# riffle-CT-beta-0_1_0.net
KiCad netlist of a schematic drawn in EAGLE
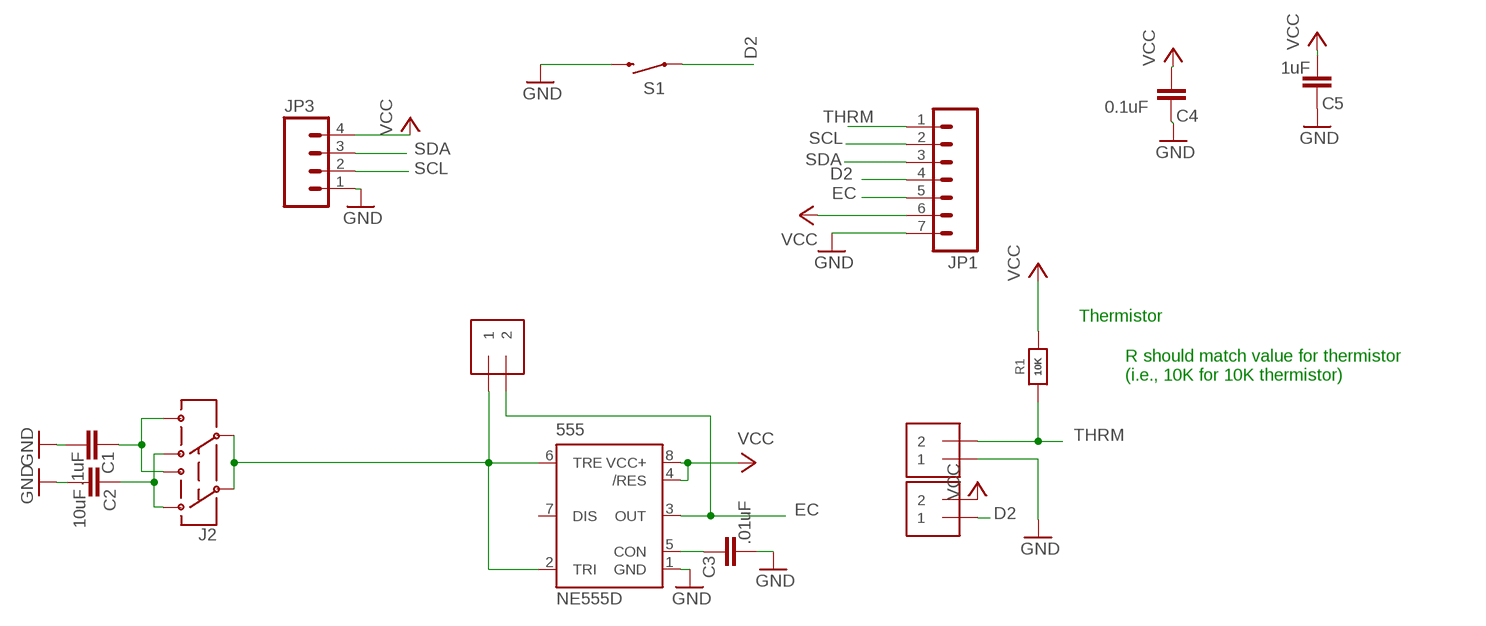
[diagram p0: schematic, sheet 1]

(export (version "E")
  (design (tool "Eeschema 10.0.6"))
  (components
    (comp (ref "1W")
      (value "1X2-3.5MM")
      (footprint "eagle-import:1X2-3.5MM")
      (libsource (lib "eagle-import") (part "1X2-3.5MM"))
    )
    (comp (ref "555")
      (value "NE555D")
      (footprint "eagle-import:SO08@1")
      (libsource (lib "eagle-import") (part "NE555D"))
    )
    (comp (ref "C1")
      (value ".1uF")
      (footprint "eagle-import:0603-CAP")
      (libsource (lib "eagle-import") (part "CAP0603-CAP"))
    )
    (comp (ref "C2")
      (value "10uF")
      (footprint "eagle-import:0603-CAP")
      (libsource (lib "eagle-import") (part "CAP0603-CAP"))
    )
    (comp (ref "C3")
      (value ".01uF")
      (footprint "eagle-import:0603-CAP")
      (libsource (lib "eagle-import") (part "CAP0603-CAP"))
    )
    (comp (ref "C4")
      (value "0.1uF")
      (footprint "eagle-import:0603-CAP")
      (libsource (lib "eagle-import") (part "CAP0603-CAP"))
    )
    (comp (ref "C5")
      (value "1uF")
      (footprint "eagle-import:0603-CAP")
      (libsource (lib "eagle-import") (part "CAP0603-CAP"))
    )
    (comp (ref "EC")
      (value "1X2-3.5MM")
      (footprint "eagle-import:1X2-3.5MM")
      (libsource (lib "eagle-import") (part "1X2-3.5MM"))
    )
    (comp (ref "J2")
      (value "AYZ0202")
      (footprint "eagle-import:AYZ0202")
      (libsource (lib "eagle-import") (part "AYZ0202"))
    )
    (comp (ref "JP1")
      (value "M07")
      (footprint "eagle-import:1X07")
      (libsource (lib "eagle-import") (part "M07"))
    )
    (comp (ref "JP3")
      (value "M04SMD")
      (footprint "eagle-import:1X04-SMD")
      (libsource (lib "eagle-import") (part "M04SMD"))
    )
    (comp (ref "R1")
      (value "10K")
      (footprint "eagle-import:0603-NO")
      (libsource (lib "eagle-import") (part "RESISTOR_0603_NOOUT"))
    )
    (comp (ref "S1")
      (value "REED")
      (footprint "eagle-import:REED_SWITCH_PLASTIC")
      (libsource (lib "eagle-import") (part "SWITCH-MOMENTARY-2PTH_REED2"))
    )
    (comp (ref "THRM")
      (value "1X2-3.5MM")
      (footprint "eagle-import:1X2-3.5MM")
      (libsource (lib "eagle-import") (part "1X2-3.5MM"))
    )
  )
  (nets
    (net (code "1") (name "/D2") (class "Default")
      (node (ref "1W") (pin "1") (pinfunction "1_1") (pintype "passive"))
      (node (ref "JP1") (pin "4") (pinfunction "4_4") (pintype "passive"))
      (node (ref "S1") (pin "P$1") (pinfunction "1_P$1") (pintype "passive"))
    )
    (net (code "2") (name "/EC") (class "Default")
      (node (ref "555") (pin "3") (pinfunction "OUT_3") (pintype "output"))
      (node (ref "EC") (pin "2") (pinfunction "2_2") (pintype "passive"))
      (node (ref "JP1") (pin "5") (pinfunction "5_5") (pintype "passive"))
    )
    (net (code "3") (name "/SCL") (class "Default")
      (node (ref "JP1") (pin "2") (pinfunction "2_2") (pintype "passive"))
      (node (ref "JP3") (pin "2") (pinfunction "2_2") (pintype "passive"))
    )
    (net (code "4") (name "/SDA") (class "Default")
      (node (ref "JP1") (pin "3") (pinfunction "3_3") (pintype "passive"))
      (node (ref "JP3") (pin "3") (pinfunction "3_3") (pintype "passive"))
    )
    (net (code "5") (name "/THRM") (class "Default")
      (node (ref "JP1") (pin "1") (pinfunction "1_1") (pintype "passive"))
      (node (ref "R1") (pin "1") (pinfunction "1_1") (pintype "passive"))
      (node (ref "THRM") (pin "2") (pinfunction "2_2") (pintype "passive"))
    )
    (net (code "6") (name "GND") (class "Default")
      (node (ref "555") (pin "1") (pinfunction "GND_1") (pintype "power_in"))
      (node (ref "C1") (pin "1") (pinfunction "1_1") (pintype "passive"))
      (node (ref "C2") (pin "1") (pinfunction "1_1") (pintype "passive"))
      (node (ref "C3") (pin "1") (pinfunction "1_1") (pintype "passive"))
      (node (ref "C4") (pin "2") (pinfunction "2_2") (pintype "passive"))
      (node (ref "C5") (pin "2") (pinfunction "2_2") (pintype "passive"))
      (node (ref "JP1") (pin "7") (pinfunction "7_7") (pintype "passive"))
      (node (ref "JP3") (pin "1") (pinfunction "1_1") (pintype "passive"))
      (node (ref "S1") (pin "P$2") (pinfunction "2_P$2") (pintype "passive"))
      (node (ref "THRM") (pin "1") (pinfunction "1_1") (pintype "passive"))
    )
    (net (code "7") (name "Net-(555-CON)") (class "Default")
      (node (ref "555") (pin "5") (pinfunction "CON_5") (pintype "input"))
      (node (ref "C3") (pin "2") (pinfunction "2_2") (pintype "passive"))
    )
    (net (code "8") (name "Net-(555-TRE)") (class "Default")
      (node (ref "555") (pin "2") (pinfunction "TRI_2") (pintype "input"))
      (node (ref "555") (pin "6") (pinfunction "TRE_6") (pintype "input"))
      (node (ref "EC") (pin "1") (pinfunction "1_1") (pintype "passive"))
      (node (ref "J2") (pin "2") (pinfunction "2_2") (pintype "bidirectional"))
      (node (ref "J2") (pin "5") (pinfunction "5_5") (pintype "bidirectional"))
    )
    (net (code "9") (name "Net-(J2-1)") (class "Default")
      (node (ref "C2") (pin "2") (pinfunction "2_2") (pintype "passive"))
      (node (ref "J2") (pin "3") (pinfunction "1_3") (pintype "bidirectional"))
      (node (ref "J2") (pin "6") (pinfunction "4_6") (pintype "bidirectional"))
    )
    (net (code "10") (name "Net-(J2-3)") (class "Default")
      (node (ref "C1") (pin "2") (pinfunction "2_2") (pintype "passive"))
      (node (ref "J2") (pin "1") (pinfunction "3_1") (pintype "bidirectional"))
      (node (ref "J2") (pin "4") (pinfunction "6_4") (pintype "bidirectional"))
    )
    (net (code "11") (name "VCC") (class "Default")
      (node (ref "1W") (pin "2") (pinfunction "2_2") (pintype "passive"))
      (node (ref "555") (pin "4") (pinfunction "/RES_4") (pintype "input"))
      (node (ref "555") (pin "8") (pinfunction "VCC+_8") (pintype "power_in"))
      (node (ref "C4") (pin "1") (pinfunction "1_1") (pintype "passive"))
      (node (ref "C5") (pin "1") (pinfunction "1_1") (pintype "passive"))
      (node (ref "JP1") (pin "6") (pinfunction "6_6") (pintype "passive"))
      (node (ref "JP3") (pin "4") (pinfunction "4_4") (pintype "passive"))
      (node (ref "R1") (pin "2") (pinfunction "2_2") (pintype "passive"))
    )
    (net (code "12") (name "unconnected-(555-DIS-Pad7)") (class "Default")
      (node (ref "555") (pin "7") (pinfunction "DIS_7") (pintype "input"))
    )
  )
)
